# Arduino_Shield.net
KiCad netlist of a schematic drawn in EAGLE
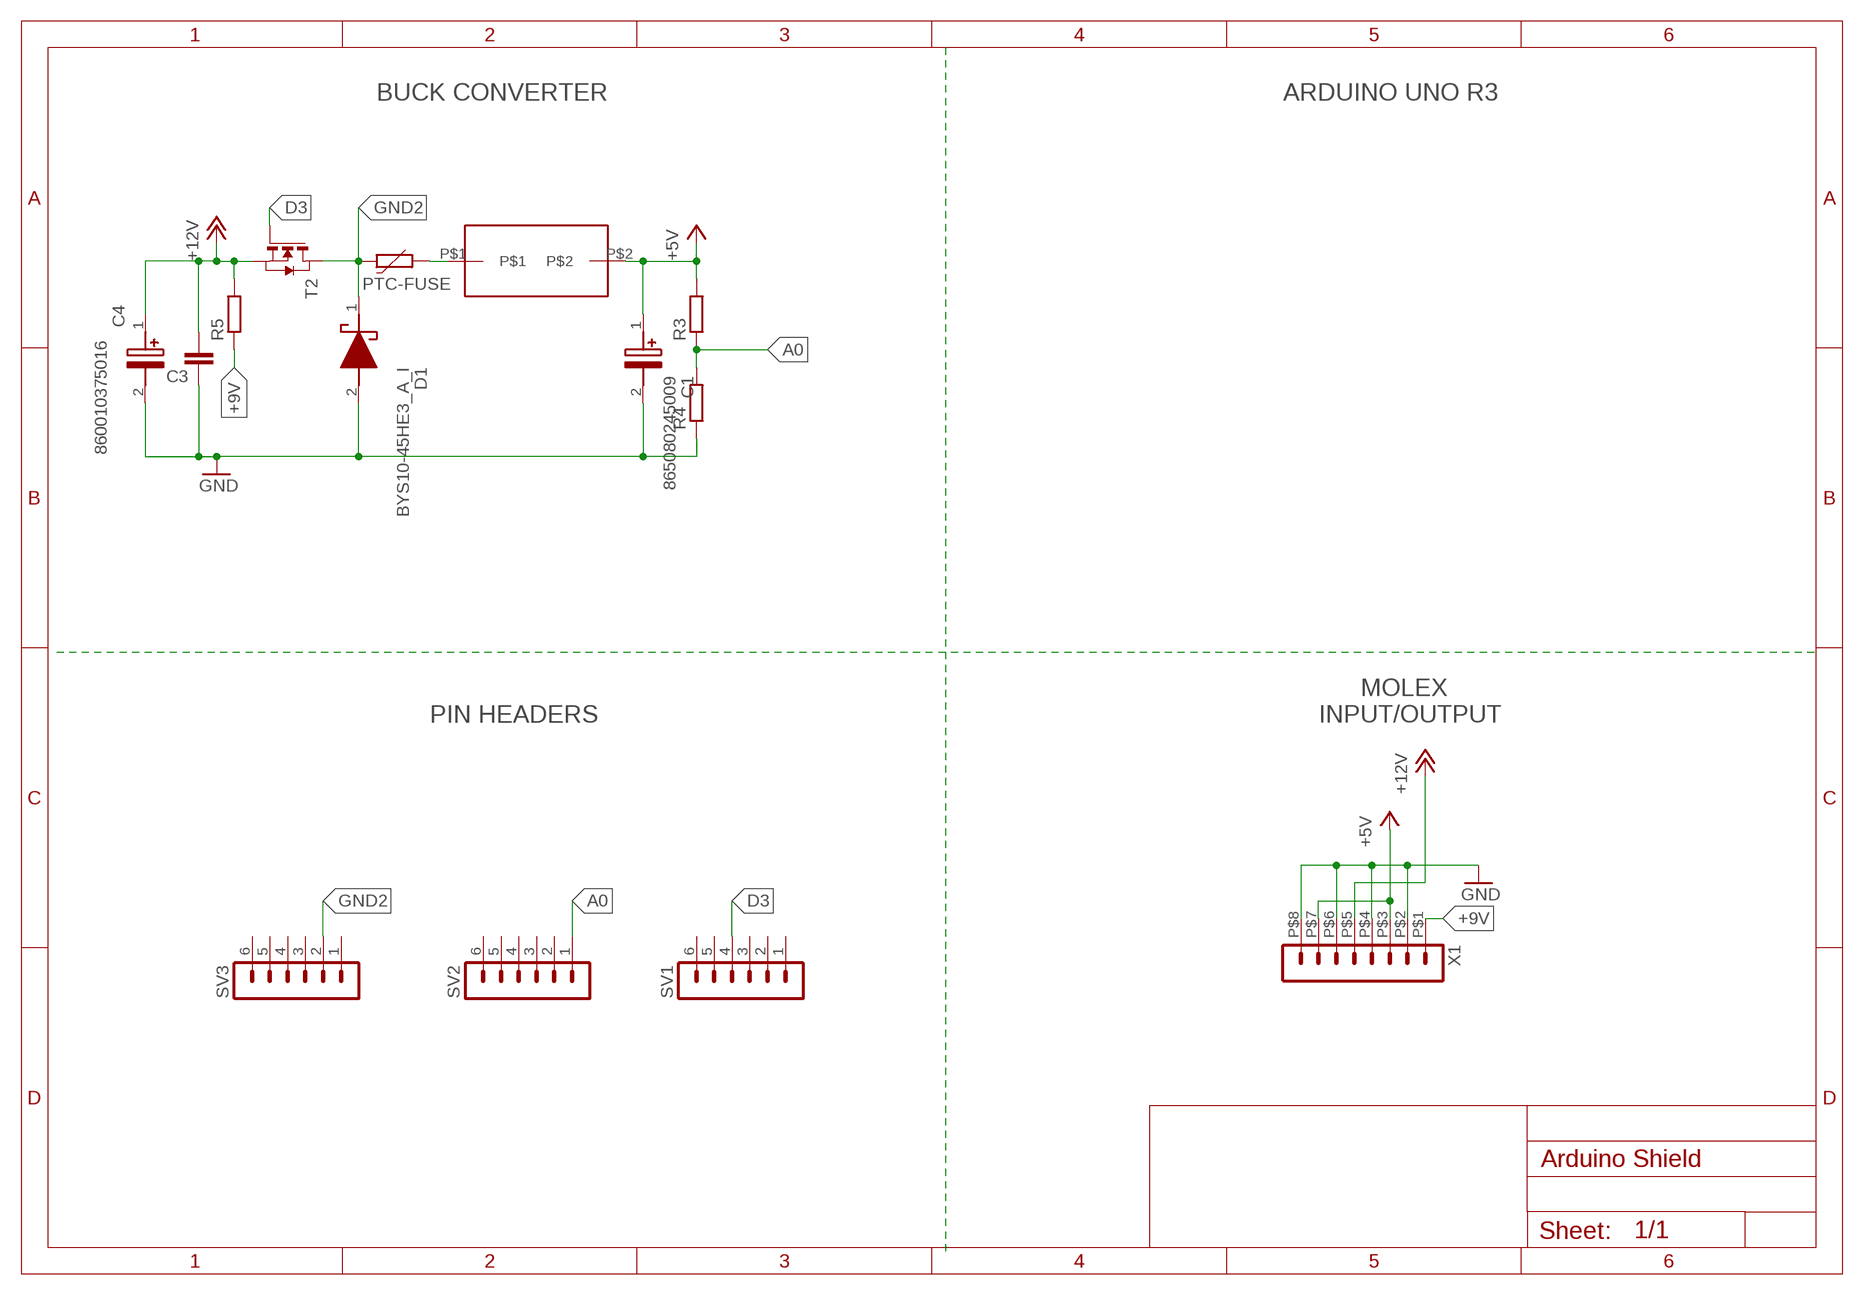
[diagram p0: schematic, sheet 1]

(export (version "E")
  (design (tool "Eeschema 10.0.6"))
  (components
    (comp (ref "C1")
      (value "865080245009")
      (footprint "eagle-import:CAPAE660X770N")
      (fields (field (name "MOUSER_PART_NUMBER") "710-865080245009"))
      (libsource (lib "eagle-import") (part "865080245009"))
    )
    (comp (ref "C3")
      (value "C-EUC1206K")
      (footprint "eagle-import:C1206K")
      (libsource (lib "eagle-import") (part "C-EUC1206K"))
    )
    (comp (ref "C4")
      (value "860010375016")
      (footprint "eagle-import:CAPPRD500W62D1000H1750")
      (fields (field (name "MOUSER_PART_NUMBER") "710-860010375016"))
      (libsource (lib "eagle-import") (part "860010375016"))
    )
    (comp (ref "D1")
      (value "BYS10-45HE3_A_I")
      (footprint "eagle-import:DIOM5127X229N")
      (fields
        (field (name "MANUFACTURER_PART_NUMBER") "BYS10-45HE3_A/I")
        (field (name "MOUSER_PART_NUMBER") "78-BYS10-45HE3_A/I")
      )
      (libsource (lib "eagle-import") (part "BYS10-45HE3_A_I"))
    )
    (comp (ref "FUSE")
      (value "PTC-FUSE")
      (footprint "eagle-import:1206")
      (libsource (lib "eagle-import") (part "PTC-FUSE"))
    )
    (comp (ref "R3")
      (value "R-EU_R1206")
      (footprint "eagle-import:R1206")
      (libsource (lib "eagle-import") (part "R-EU_R1206"))
    )
    (comp (ref "R4")
      (value "R-EU_R1206")
      (footprint "eagle-import:R1206")
      (libsource (lib "eagle-import") (part "R-EU_R1206"))
    )
    (comp (ref "R5")
      (value "R-EU_R1206")
      (footprint "eagle-import:R1206")
      (libsource (lib "eagle-import") (part "R-EU_R1206"))
    )
    (comp (ref "SV1")
      (value "MA06-1_PINHEADERS")
      (footprint "eagle-import:MA06-1")
      (libsource (lib "eagle-import") (part "MA06-1_PINHEADERS"))
    )
    (comp (ref "SV2")
      (value "MA06-1_PINHEADERS")
      (footprint "eagle-import:MA06-1")
      (libsource (lib "eagle-import") (part "MA06-1_PINHEADERS"))
    )
    (comp (ref "SV3")
      (value "MA06-1_PINHEADERS")
      (footprint "eagle-import:MA06-1")
      (libsource (lib "eagle-import") (part "MA06-1_PINHEADERS"))
    )
    (comp (ref "T2")
      (value "NMOSSOT23")
      (footprint "eagle-import:SOT-23")
      (libsource (lib "eagle-import") (part "NMOSSOT23"))
    )
    (comp (ref "U$2")
      (value "DR1050-INDUCTOR")
      (footprint "eagle-import:DR1050-INDUCTOR")
      (libsource (lib "eagle-import") (part "DR1050-INDUCTOR"))
    )
    (comp (ref "X1")
      (value "HEADER_POS8_43045-0812")
      (footprint "eagle-import:43045-0812")
      (libsource (lib "eagle-import") (part "HEADER_POS8_?43045-0812"))
    )
  )
  (nets
    (net (code "1") (name "+5V") (class "Default")
      (node (ref "C1") (pin "1") (pinfunction "+_1") (pintype "bidirectional"))
      (node (ref "R3") (pin "2") (pinfunction "2_2") (pintype "passive"))
      (node (ref "U$2") (pin "P$2") (pinfunction "P$2_P$2") (pintype "bidirectional"))
      (node (ref "X1") (pin "P$3") (pinfunction "3_P$3") (pintype "passive"))
      (node (ref "X1") (pin "P$7") (pinfunction "7_P$7") (pintype "passive"))
    )
    (net (code "2") (name "+9V") (class "Default")
      (node (ref "R5") (pin "1") (pinfunction "1_1") (pintype "passive"))
      (node (ref "X1") (pin "P$1") (pinfunction "1_P$1") (pintype "passive"))
    )
    (net (code "3") (name "+12V") (class "Default")
      (node (ref "C3") (pin "2") (pinfunction "2_2") (pintype "passive"))
      (node (ref "C4") (pin "1") (pinfunction "+_1") (pintype "bidirectional"))
      (node (ref "R5") (pin "2") (pinfunction "2_2") (pintype "passive"))
      (node (ref "T2") (pin "2") (pinfunction "S_2") (pintype "passive"))
      (node (ref "X1") (pin "P$5") (pinfunction "5_P$5") (pintype "passive"))
    )
    (net (code "4") (name "A0") (class "Default")
      (node (ref "R3") (pin "1") (pinfunction "1_1") (pintype "passive"))
      (node (ref "R4") (pin "2") (pinfunction "2_2") (pintype "passive"))
      (node (ref "SV2") (pin "1") (pinfunction "1_1") (pintype "passive"))
    )
    (net (code "5") (name "D3") (class "Default")
      (node (ref "SV1") (pin "4") (pinfunction "4_4") (pintype "passive"))
      (node (ref "T2") (pin "3") (pinfunction "G_3") (pintype "passive"))
    )
    (net (code "6") (name "GND") (class "Default")
      (node (ref "C1") (pin "2") (pinfunction "-_2") (pintype "bidirectional"))
      (node (ref "C3") (pin "1") (pinfunction "1_1") (pintype "passive"))
      (node (ref "C4") (pin "2") (pinfunction "-_2") (pintype "bidirectional"))
      (node (ref "D1") (pin "2") (pinfunction "A_2") (pintype "bidirectional"))
      (node (ref "R4") (pin "1") (pinfunction "1_1") (pintype "passive"))
      (node (ref "X1") (pin "P$2") (pinfunction "2_P$2") (pintype "passive"))
      (node (ref "X1") (pin "P$4") (pinfunction "4_P$4") (pintype "passive"))
      (node (ref "X1") (pin "P$6") (pinfunction "6_P$6") (pintype "passive"))
      (node (ref "X1") (pin "P$8") (pinfunction "8_P$8") (pintype "passive"))
    )
    (net (code "7") (name "GND2") (class "Default")
      (node (ref "D1") (pin "1") (pinfunction "K_1") (pintype "bidirectional"))
      (node (ref "FUSE") (pin "1") (pinfunction "1_1") (pintype "passive"))
      (node (ref "SV3") (pin "2") (pinfunction "2_2") (pintype "passive"))
      (node (ref "T2") (pin "1") (pinfunction "D_1") (pintype "passive"))
    )
    (net (code "8") (name "Net-(FUSE-Pad2)") (class "Default")
      (node (ref "FUSE") (pin "2") (pinfunction "2_2") (pintype "passive"))
      (node (ref "U$2") (pin "P$1") (pinfunction "P$1_P$1") (pintype "bidirectional"))
    )
    (net (code "9") (name "unconnected-(SV1-Pad1)") (class "Default")
      (node (ref "SV1") (pin "1") (pinfunction "1_1") (pintype "passive"))
    )
    (net (code "10") (name "unconnected-(SV1-Pad2)") (class "Default")
      (node (ref "SV1") (pin "2") (pinfunction "2_2") (pintype "passive"))
    )
    (net (code "11") (name "unconnected-(SV1-Pad3)") (class "Default")
      (node (ref "SV1") (pin "3") (pinfunction "3_3") (pintype "passive"))
    )
    (net (code "12") (name "unconnected-(SV1-Pad5)") (class "Default")
      (node (ref "SV1") (pin "5") (pinfunction "5_5") (pintype "passive"))
    )
    (net (code "13") (name "unconnected-(SV1-Pad6)") (class "Default")
      (node (ref "SV1") (pin "6") (pinfunction "6_6") (pintype "passive"))
    )
    (net (code "14") (name "unconnected-(SV2-Pad2)") (class "Default")
      (node (ref "SV2") (pin "2") (pinfunction "2_2") (pintype "passive"))
    )
    (net (code "15") (name "unconnected-(SV2-Pad3)") (class "Default")
      (node (ref "SV2") (pin "3") (pinfunction "3_3") (pintype "passive"))
    )
    (net (code "16") (name "unconnected-(SV2-Pad4)") (class "Default")
      (node (ref "SV2") (pin "4") (pinfunction "4_4") (pintype "passive"))
    )
    (net (code "17") (name "unconnected-(SV2-Pad5)") (class "Default")
      (node (ref "SV2") (pin "5") (pinfunction "5_5") (pintype "passive"))
    )
    (net (code "18") (name "unconnected-(SV2-Pad6)") (class "Default")
      (node (ref "SV2") (pin "6") (pinfunction "6_6") (pintype "passive"))
    )
    (net (code "19") (name "unconnected-(SV3-Pad1)") (class "Default")
      (node (ref "SV3") (pin "1") (pinfunction "1_1") (pintype "passive"))
    )
    (net (code "20") (name "unconnected-(SV3-Pad3)") (class "Default")
      (node (ref "SV3") (pin "3") (pinfunction "3_3") (pintype "passive"))
    )
    (net (code "21") (name "unconnected-(SV3-Pad4)") (class "Default")
      (node (ref "SV3") (pin "4") (pinfunction "4_4") (pintype "passive"))
    )
    (net (code "22") (name "unconnected-(SV3-Pad5)") (class "Default")
      (node (ref "SV3") (pin "5") (pinfunction "5_5") (pintype "passive"))
    )
    (net (code "23") (name "unconnected-(SV3-Pad6)") (class "Default")
      (node (ref "SV3") (pin "6") (pinfunction "6_6") (pintype "passive"))
    )
  )
)
